# sign_filter.net
KiCad netlist of a schematic drawn in Altium Designer
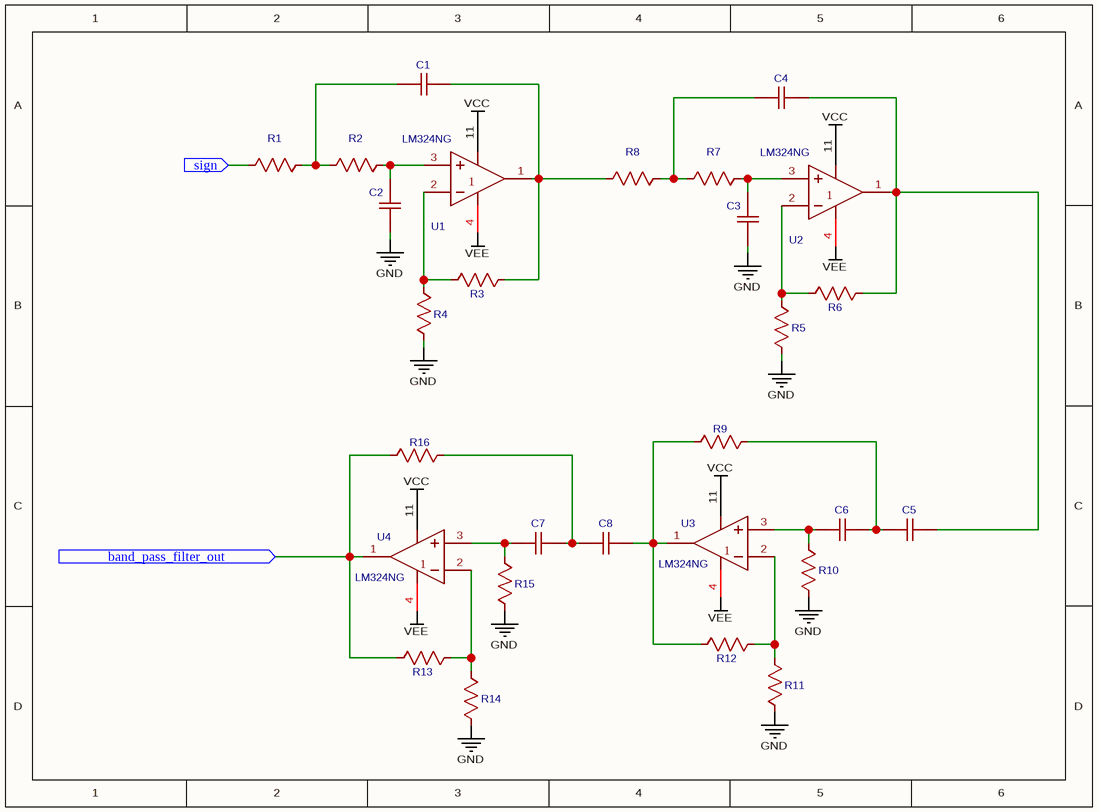
[diagram p0: sign_filter.schdoc]

(export (version "E")
  (design (tool "Eeschema 10.0.6"))
  (components
    (comp (ref "C1")
      (value "0.1u")
      (fields (field (name "CONTRIBUTOR") "LCEDA_Lib"))
      (libsource (lib "altium-import") (part "root_0_0.1u_"))
    )
    (comp (ref "C2")
      (value "0.1u")
      (fields (field (name "CONTRIBUTOR") "LCEDA_Lib"))
      (libsource (lib "altium-import") (part "root_1_0.1u_"))
    )
    (comp (ref "C3")
      (value "0.1u")
      (fields (field (name "CONTRIBUTOR") "LCEDA_Lib"))
      (libsource (lib "altium-import") (part "root_1_0.1u_"))
    )
    (comp (ref "C4")
      (value "0.1u")
      (fields (field (name "CONTRIBUTOR") "LCEDA_Lib"))
      (libsource (lib "altium-import") (part "root_0_0.1u_"))
    )
    (comp (ref "C5")
      (value "0.1u")
      (fields (field (name "CONTRIBUTOR") "LCEDA_Lib"))
      (libsource (lib "altium-import") (part "root_0_0.1u_"))
    )
    (comp (ref "C6")
      (value "0.1u")
      (fields (field (name "CONTRIBUTOR") "LCEDA_Lib"))
      (libsource (lib "altium-import") (part "root_0_0.1u_"))
    )
    (comp (ref "C7")
      (value "0.1u")
      (fields (field (name "CONTRIBUTOR") "LCEDA_Lib"))
      (libsource (lib "altium-import") (part "root_0_0.1u_"))
    )
    (comp (ref "C8")
      (value "0.1u")
      (fields (field (name "CONTRIBUTOR") "LCEDA_Lib"))
      (libsource (lib "altium-import") (part "root_0_0.1u_"))
    )
    (comp (ref "R1")
      (value "1k")
      (fields (field (name "CONTRIBUTOR") "LCEDA_Lib"))
      (libsource (lib "altium-import") (part "root_0_1k_"))
    )
    (comp (ref "R2")
      (value "1k")
      (fields (field (name "CONTRIBUTOR") "LCEDA_Lib"))
      (libsource (lib "altium-import") (part "root_0_1k_"))
    )
    (comp (ref "R3")
      (value "1k")
      (fields (field (name "CONTRIBUTOR") "LCEDA_Lib"))
      (libsource (lib "altium-import") (part "root_0_1k_"))
    )
    (comp (ref "R4")
      (value "1k")
      (fields (field (name "CONTRIBUTOR") "LCEDA_Lib"))
      (libsource (lib "altium-import") (part "root_3_1k_"))
    )
    (comp (ref "R5")
      (value "1k")
      (fields (field (name "CONTRIBUTOR") "LCEDA_Lib"))
      (libsource (lib "altium-import") (part "root_3_1k_"))
    )
    (comp (ref "R6")
      (value "1k")
      (fields (field (name "CONTRIBUTOR") "LCEDA_Lib"))
      (libsource (lib "altium-import") (part "root_0_1k_"))
    )
    (comp (ref "R7")
      (value "1k")
      (fields (field (name "CONTRIBUTOR") "LCEDA_Lib"))
      (libsource (lib "altium-import") (part "root_0_1k_"))
    )
    (comp (ref "R8")
      (value "1k")
      (fields (field (name "CONTRIBUTOR") "LCEDA_Lib"))
      (libsource (lib "altium-import") (part "root_0_1k_"))
    )
    (comp (ref "R9")
      (value "1k")
      (fields (field (name "CONTRIBUTOR") "LCEDA_Lib"))
      (libsource (lib "altium-import") (part "root_2_1k_"))
    )
    (comp (ref "R10")
      (value "1k")
      (fields (field (name "CONTRIBUTOR") "LCEDA_Lib"))
      (libsource (lib "altium-import") (part "root_1_1k_"))
    )
    (comp (ref "R11")
      (value "1k")
      (fields (field (name "CONTRIBUTOR") "LCEDA_Lib"))
      (libsource (lib "altium-import") (part "root_1_1k_"))
    )
    (comp (ref "R12")
      (value "1k")
      (fields (field (name "CONTRIBUTOR") "LCEDA_Lib"))
      (libsource (lib "altium-import") (part "root_0_1k_"))
    )
    (comp (ref "R13")
      (value "1k")
      (fields (field (name "CONTRIBUTOR") "LCEDA_Lib"))
      (libsource (lib "altium-import") (part "root_0_1k_"))
    )
    (comp (ref "R14")
      (value "1k")
      (fields (field (name "CONTRIBUTOR") "LCEDA_Lib"))
      (libsource (lib "altium-import") (part "root_1_1k_"))
    )
    (comp (ref "R15")
      (value "1k")
      (fields (field (name "CONTRIBUTOR") "LCEDA_Lib"))
      (libsource (lib "altium-import") (part "root_1_1k_"))
    )
    (comp (ref "R16")
      (value "1k")
      (fields (field (name "CONTRIBUTOR") "LCEDA_Lib"))
      (libsource (lib "altium-import") (part "root_2_1k_"))
    )
    (comp (ref "U1")
      (value "LM324NG")
      (fields
        (field (name "BOM_SUPPLIER PART") "C99121")
        (field (name "BOM_MANUFACTURER PART") "ON")
        (field (name "SUBPART_NO") "1")
      )
      (libsource (lib "altium-import") (part "root_0_LM324NG_"))
    )
    (comp (ref "U2")
      (value "LM324NG")
      (fields
        (field (name "BOM_SUPPLIER PART") "C99121")
        (field (name "BOM_MANUFACTURER PART") "ON")
        (field (name "SUBPART_NO") "1")
      )
      (libsource (lib "altium-import") (part "root_0_LM324NG_"))
    )
    (comp (ref "U3")
      (value "LM324NG")
      (fields
        (field (name "BOM_SUPPLIER PART") "C99121")
        (field (name "BOM_MANUFACTURER PART") "ON")
        (field (name "SUBPART_NO") "1")
      )
      (libsource (lib "altium-import") (part "root_2_LM324NG_"))
    )
    (comp (ref "U4")
      (value "LM324NG")
      (fields
        (field (name "BOM_SUPPLIER PART") "C99121")
        (field (name "BOM_MANUFACTURER PART") "ON")
        (field (name "SUBPART_NO") "1")
      )
      (libsource (lib "altium-import") (part "root_2_LM324NG_"))
    )
  )
  (nets
    (net (code "1") (name "/band_pass_filter_out") (class "Default")
      (node (ref "R13") (pin "1") (pinfunction "1_1") (pintype "passive"))
      (node (ref "R16") (pin "2") (pinfunction "2_2") (pintype "passive"))
      (node (ref "U4") (pin "1") (pinfunction "OUT1_1") (pintype "passive"))
    )
    (net (code "2") (name "/sign") (class "Default")
      (node (ref "R1") (pin "1") (pinfunction "1_1") (pintype "passive"))
    )
    (net (code "3") (name "GND") (class "Default")
      (node (ref "C2") (pin "1") (pinfunction "1_1") (pintype "passive"))
      (node (ref "C3") (pin "1") (pinfunction "1_1") (pintype "passive"))
      (node (ref "R10") (pin "1") (pinfunction "1_1") (pintype "passive"))
      (node (ref "R11") (pin "1") (pinfunction "1_1") (pintype "passive"))
      (node (ref "R14") (pin "1") (pinfunction "1_1") (pintype "passive"))
      (node (ref "R15") (pin "1") (pinfunction "1_1") (pintype "passive"))
      (node (ref "R4") (pin "2") (pinfunction "2_2") (pintype "passive"))
      (node (ref "R5") (pin "2") (pinfunction "2_2") (pintype "passive"))
    )
    (net (code "4") (name "Net-(C1-Pad1)") (class "Default")
      (node (ref "C1") (pin "1") (pinfunction "1_1") (pintype "passive"))
      (node (ref "R1") (pin "2") (pinfunction "2_2") (pintype "passive"))
      (node (ref "R2") (pin "1") (pinfunction "1_1") (pintype "passive"))
    )
    (net (code "5") (name "Net-(C4-Pad1)") (class "Default")
      (node (ref "C4") (pin "1") (pinfunction "1_1") (pintype "passive"))
      (node (ref "R7") (pin "1") (pinfunction "1_1") (pintype "passive"))
      (node (ref "R8") (pin "2") (pinfunction "2_2") (pintype "passive"))
    )
    (net (code "6") (name "Net-(C5-Pad1)") (class "Default")
      (node (ref "C5") (pin "1") (pinfunction "1_1") (pintype "passive"))
      (node (ref "C6") (pin "2") (pinfunction "2_2") (pintype "passive"))
      (node (ref "R9") (pin "1") (pinfunction "1_1") (pintype "passive"))
    )
    (net (code "7") (name "Net-(C7-Pad2)") (class "Default")
      (node (ref "C7") (pin "2") (pinfunction "2_2") (pintype "passive"))
      (node (ref "C8") (pin "1") (pinfunction "1_1") (pintype "passive"))
      (node (ref "R16") (pin "1") (pinfunction "1_1") (pintype "passive"))
    )
    (net (code "8") (name "Net-(U1-IN1+)") (class "Default")
      (node (ref "C2") (pin "2") (pinfunction "2_2") (pintype "passive"))
      (node (ref "R2") (pin "2") (pinfunction "2_2") (pintype "passive"))
      (node (ref "U1") (pin "3") (pinfunction "IN1+_3") (pintype "passive"))
    )
    (net (code "9") (name "Net-(U1-IN1-)") (class "Default")
      (node (ref "R3") (pin "1") (pinfunction "1_1") (pintype "passive"))
      (node (ref "R4") (pin "1") (pinfunction "1_1") (pintype "passive"))
      (node (ref "U1") (pin "2") (pinfunction "IN1-_2") (pintype "passive"))
    )
    (net (code "10") (name "Net-(U1-OUT1)") (class "Default")
      (node (ref "C1") (pin "2") (pinfunction "2_2") (pintype "passive"))
      (node (ref "R3") (pin "2") (pinfunction "2_2") (pintype "passive"))
      (node (ref "R8") (pin "1") (pinfunction "1_1") (pintype "passive"))
      (node (ref "U1") (pin "1") (pinfunction "OUT1_1") (pintype "passive"))
    )
    (net (code "11") (name "Net-(U2-IN1+)") (class "Default")
      (node (ref "C3") (pin "2") (pinfunction "2_2") (pintype "passive"))
      (node (ref "R7") (pin "2") (pinfunction "2_2") (pintype "passive"))
      (node (ref "U2") (pin "3") (pinfunction "IN1+_3") (pintype "passive"))
    )
    (net (code "12") (name "Net-(U2-IN1-)") (class "Default")
      (node (ref "R5") (pin "1") (pinfunction "1_1") (pintype "passive"))
      (node (ref "R6") (pin "1") (pinfunction "1_1") (pintype "passive"))
      (node (ref "U2") (pin "2") (pinfunction "IN1-_2") (pintype "passive"))
    )
    (net (code "13") (name "Net-(U2-OUT1)") (class "Default")
      (node (ref "C4") (pin "2") (pinfunction "2_2") (pintype "passive"))
      (node (ref "C5") (pin "2") (pinfunction "2_2") (pintype "passive"))
      (node (ref "R6") (pin "2") (pinfunction "2_2") (pintype "passive"))
      (node (ref "U2") (pin "1") (pinfunction "OUT1_1") (pintype "passive"))
    )
    (net (code "14") (name "Net-(U3-IN1+)") (class "Default")
      (node (ref "C6") (pin "1") (pinfunction "1_1") (pintype "passive"))
      (node (ref "R10") (pin "2") (pinfunction "2_2") (pintype "passive"))
      (node (ref "U3") (pin "3") (pinfunction "IN1+_3") (pintype "passive"))
    )
    (net (code "15") (name "Net-(U3-IN1-)") (class "Default")
      (node (ref "R11") (pin "2") (pinfunction "2_2") (pintype "passive"))
      (node (ref "R12") (pin "2") (pinfunction "2_2") (pintype "passive"))
      (node (ref "U3") (pin "2") (pinfunction "IN1-_2") (pintype "passive"))
    )
    (net (code "16") (name "Net-(U3-OUT1)") (class "Default")
      (node (ref "C8") (pin "2") (pinfunction "2_2") (pintype "passive"))
      (node (ref "R12") (pin "1") (pinfunction "1_1") (pintype "passive"))
      (node (ref "R9") (pin "2") (pinfunction "2_2") (pintype "passive"))
      (node (ref "U3") (pin "1") (pinfunction "OUT1_1") (pintype "passive"))
    )
    (net (code "17") (name "Net-(U4-IN1+)") (class "Default")
      (node (ref "C7") (pin "1") (pinfunction "1_1") (pintype "passive"))
      (node (ref "R15") (pin "2") (pinfunction "2_2") (pintype "passive"))
      (node (ref "U4") (pin "3") (pinfunction "IN1+_3") (pintype "passive"))
    )
    (net (code "18") (name "Net-(U4-IN1-)") (class "Default")
      (node (ref "R13") (pin "2") (pinfunction "2_2") (pintype "passive"))
      (node (ref "R14") (pin "2") (pinfunction "2_2") (pintype "passive"))
      (node (ref "U4") (pin "2") (pinfunction "IN1-_2") (pintype "passive"))
    )
    (net (code "19") (name "VCC") (class "Default")
      (node (ref "U1") (pin "11") (pinfunction "GND_11") (pintype "passive"))
      (node (ref "U2") (pin "11") (pinfunction "GND_11") (pintype "passive"))
      (node (ref "U3") (pin "11") (pinfunction "GND_11") (pintype "passive"))
      (node (ref "U4") (pin "11") (pinfunction "GND_11") (pintype "passive"))
    )
    (net (code "20") (name "VEE") (class "Default")
      (node (ref "U1") (pin "4") (pinfunction "VCC_4") (pintype "passive"))
      (node (ref "U2") (pin "4") (pinfunction "VCC_4") (pintype "passive"))
      (node (ref "U3") (pin "4") (pinfunction "VCC_4") (pintype "passive"))
      (node (ref "U4") (pin "4") (pinfunction "VCC_4") (pintype "passive"))
    )
  )
)
